# PowerMeasure.net
KiCad netlist of a schematic drawn in Altium Designer
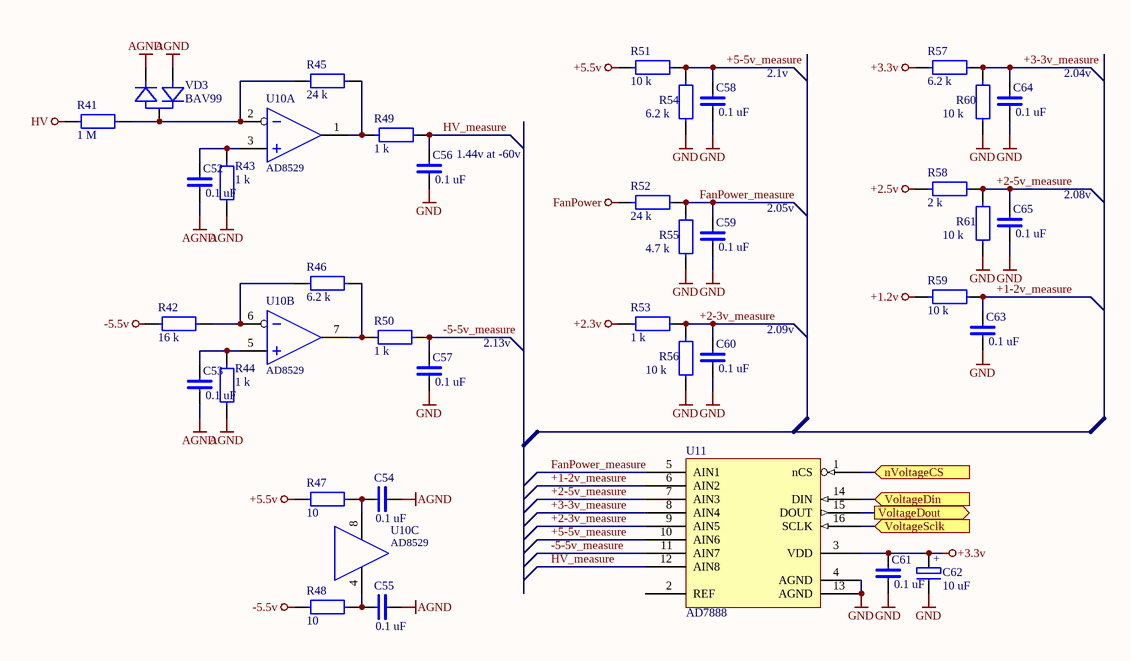
[diagram p0: PowerMeasure.SchDoc]

(export (version "E")
  (design (tool "Eeschema 10.0.6"))
  (components
    (comp (ref "C52") (value "0.1 uF") (footprint "0603") (libsource (lib "*") (part "C")))
    (comp (ref "C53") (value "0.1 uF") (footprint "0603") (libsource (lib "*") (part "C")))
    (comp (ref "C54") (value "0.1 uF") (libsource (lib "Adevice") (part "c")))
    (comp (ref "C55") (value "0.1 uF") (libsource (lib "Adevice") (part "c")))
    (comp (ref "C56") (value "0.1 uF") (footprint "0603") (libsource (lib "*") (part "C")))
    (comp (ref "C57") (value "0.1 uF") (footprint "0603") (libsource (lib "*") (part "C")))
    (comp (ref "C58") (value "0.1 uF") (footprint "0603") (libsource (lib "*") (part "C")))
    (comp (ref "C59") (value "0.1 uF") (footprint "0603") (libsource (lib "*") (part "C")))
    (comp (ref "C60") (value "0.1 uF") (footprint "0603") (libsource (lib "*") (part "C")))
    (comp (ref "C61") (value "0.1 uF") (footprint "0603") (libsource (lib "*") (part "C")))
    (comp (ref "C62") (value "10 uF") (footprint "CP3216") (libsource (lib "*") (part "C POL")))
    (comp (ref "C63") (value "0.1 uF") (footprint "0603") (libsource (lib "*") (part "C")))
    (comp (ref "C64") (value "0.1 uF") (footprint "0603") (libsource (lib "*") (part "C")))
    (comp (ref "C65") (value "0.1 uF") (footprint "0603") (libsource (lib "*") (part "C")))
    (comp (ref "R41") (value "1 M") (footprint "1206") (libsource (lib "Adevice") (part "R")))
    (comp (ref "R42") (value "16 k") (footprint "1206") (libsource (lib "Adevice") (part "R")))
    (comp (ref "R43") (value "1 k") (footprint "0603") (libsource (lib "Adevice") (part "R")))
    (comp (ref "R44") (value "1 k") (footprint "0603") (libsource (lib "Adevice") (part "R")))
    (comp (ref "R45") (value "24 k") (footprint "1206") (libsource (lib "Adevice") (part "R")))
    (comp (ref "R46") (value "6.2 k") (footprint "1206") (libsource (lib "Adevice") (part "R")))
    (comp (ref "R47") (value "10") (footprint "0603") (libsource (lib "Adevice") (part "R")))
    (comp (ref "R48") (value "10") (footprint "0603") (libsource (lib "Adevice") (part "R")))
    (comp (ref "R49") (value "1 k") (footprint "0603") (libsource (lib "*") (part "R")))
    (comp (ref "R50") (value "1 k") (footprint "0603") (libsource (lib "*") (part "R")))
    (comp (ref "R51") (value "10 k") (footprint "0603") (libsource (lib "*") (part "R")))
    (comp (ref "R52") (value "24 k") (footprint "1206") (libsource (lib "*") (part "R")))
    (comp (ref "R53") (value "1 k") (footprint "0603") (libsource (lib "*") (part "R")))
    (comp (ref "R54") (value "6.2 k") (footprint "1206") (libsource (lib "*") (part "R")))
    (comp (ref "R55") (value "4.7 k") (footprint "1206") (libsource (lib "*") (part "R")))
    (comp (ref "R56") (value "10 k") (footprint "0603") (libsource (lib "*") (part "R")))
    (comp (ref "R57") (value "6.2 k") (footprint "1206") (libsource (lib "*") (part "R")))
    (comp (ref "R58") (value "2 k") (footprint "1206") (libsource (lib "*") (part "R")))
    (comp (ref "R59") (value "10 k") (footprint "0603") (libsource (lib "*") (part "R")))
    (comp (ref "R60") (value "10 k") (footprint "0603") (libsource (lib "*") (part "R")))
    (comp (ref "R61") (value "10 k") (footprint "0603") (libsource (lib "*") (part "R")))
    (comp (ref "U10")
      (value "AD8529")
      (footprint "8SOIC150")
      (description "8 MHz Rail-to-Rail Operational Amplifiers")
      (libsource (lib "Mylib") (part "AD8529"))
    )
    (comp (ref "U11")
      (value "AD7888")
      (footprint "16SOIC150")
      (description "8-Channel, 125 kSPS, 12-Bit ADC")
      (libsource (lib "Mylib") (part "AD7888"))
    )
    (comp (ref "VD3")
      (value "BAV99")
      (footprint "SOT-23")
      (description "Double diode")
      (libsource (lib "Vdiode") (part "BAV99"))
    )
  )
  (nets
    (net (code "1") (name "+1.2v") (class "Default")
      (node (ref "R59") (pin "2") (pinfunction "2_2") (pintype "passive"))
    )
    (net (code "2") (name "+2.3v") (class "Default")
      (node (ref "R53") (pin "2") (pinfunction "2_2") (pintype "passive"))
    )
    (net (code "3") (name "+2.5v") (class "Default")
      (node (ref "R58") (pin "2") (pinfunction "2_2") (pintype "passive"))
    )
    (net (code "4") (name "+3.3v") (class "Default")
      (node (ref "C61") (pin "2") (pinfunction "2_2") (pintype "passive"))
      (node (ref "C62") (pin "+") (pinfunction "+_+") (pintype "passive"))
      (node (ref "R57") (pin "2") (pinfunction "2_2") (pintype "passive"))
      (node (ref "U11") (pin "3") (pinfunction "VDD_3") (pintype "passive"))
    )
    (net (code "5") (name "+5.5v") (class "Default")
      (node (ref "R47") (pin "1") (pinfunction "1_1") (pintype "passive"))
      (node (ref "R51") (pin "2") (pinfunction "2_2") (pintype "passive"))
    )
    (net (code "6") (name "-5.5v") (class "Default")
      (node (ref "R42") (pin "1") (pinfunction "1_1") (pintype "passive"))
      (node (ref "R48") (pin "1") (pinfunction "1_1") (pintype "passive"))
    )
    (net (code "7") (name "/+1-2v_measure") (class "Default")
      (node (ref "C63") (pin "2") (pinfunction "2_2") (pintype "passive"))
      (node (ref "R59") (pin "1") (pinfunction "1_1") (pintype "passive"))
      (node (ref "U11") (pin "6") (pinfunction "AIN2_6") (pintype "passive"))
    )
    (net (code "8") (name "/+2-3v_measure") (class "Default")
      (node (ref "C60") (pin "2") (pinfunction "2_2") (pintype "passive"))
      (node (ref "R53") (pin "1") (pinfunction "1_1") (pintype "passive"))
      (node (ref "R56") (pin "2") (pinfunction "2_2") (pintype "passive"))
      (node (ref "U11") (pin "9") (pinfunction "AIN5_9") (pintype "passive"))
    )
    (net (code "9") (name "/+2-5v_measure") (class "Default")
      (node (ref "C65") (pin "2") (pinfunction "2_2") (pintype "passive"))
      (node (ref "R58") (pin "1") (pinfunction "1_1") (pintype "passive"))
      (node (ref "R61") (pin "2") (pinfunction "2_2") (pintype "passive"))
      (node (ref "U11") (pin "7") (pinfunction "AIN3_7") (pintype "passive"))
    )
    (net (code "10") (name "/+3-3v_measure") (class "Default")
      (node (ref "C64") (pin "2") (pinfunction "2_2") (pintype "passive"))
      (node (ref "R57") (pin "1") (pinfunction "1_1") (pintype "passive"))
      (node (ref "R60") (pin "2") (pinfunction "2_2") (pintype "passive"))
      (node (ref "U11") (pin "8") (pinfunction "AIN4_8") (pintype "passive"))
    )
    (net (code "11") (name "/+5-5v_measure") (class "Default")
      (node (ref "C58") (pin "2") (pinfunction "2_2") (pintype "passive"))
      (node (ref "R51") (pin "1") (pinfunction "1_1") (pintype "passive"))
      (node (ref "R54") (pin "2") (pinfunction "2_2") (pintype "passive"))
      (node (ref "U11") (pin "10") (pinfunction "AIN6_10") (pintype "passive"))
    )
    (net (code "12") (name "/-5-5v_measure") (class "Default")
      (node (ref "C57") (pin "2") (pinfunction "2_2") (pintype "passive"))
      (node (ref "R50") (pin "2") (pinfunction "2_2") (pintype "passive"))
      (node (ref "U11") (pin "11") (pinfunction "AIN7_11") (pintype "passive"))
    )
    (net (code "13") (name "/FanPower_measure") (class "Default")
      (node (ref "C59") (pin "2") (pinfunction "2_2") (pintype "passive"))
      (node (ref "R52") (pin "1") (pinfunction "1_1") (pintype "passive"))
      (node (ref "R55") (pin "2") (pinfunction "2_2") (pintype "passive"))
      (node (ref "U11") (pin "5") (pinfunction "AIN1_5") (pintype "passive"))
    )
    (net (code "14") (name "/HV_measure") (class "Default")
      (node (ref "C56") (pin "2") (pinfunction "2_2") (pintype "passive"))
      (node (ref "R49") (pin "1") (pinfunction "1_1") (pintype "passive"))
      (node (ref "U11") (pin "12") (pinfunction "AIN8_12") (pintype "passive"))
    )
    (net (code "15") (name "/VoltageDin") (class "Default")
      (node (ref "U11") (pin "14") (pinfunction "DIN_14") (pintype "input"))
    )
    (net (code "16") (name "/VoltageDout") (class "Default")
      (node (ref "U11") (pin "15") (pinfunction "DOUT_15") (pintype "output"))
    )
    (net (code "17") (name "/VoltageSclk") (class "Default")
      (node (ref "U11") (pin "16") (pinfunction "SCLK_16") (pintype "input"))
    )
    (net (code "18") (name "/nVoltageCS") (class "Default")
      (node (ref "U11") (pin "1") (pinfunction "nCS_1") (pintype "input"))
    )
    (net (code "19") (name "AGND") (class "Default")
      (node (ref "C52") (pin "1") (pinfunction "1_1") (pintype "passive"))
      (node (ref "C53") (pin "1") (pinfunction "1_1") (pintype "passive"))
      (node (ref "C54") (pin "1") (pinfunction "1_1") (pintype "passive"))
      (node (ref "C55") (pin "1") (pinfunction "1_1") (pintype "passive"))
      (node (ref "R43") (pin "1") (pinfunction "1_1") (pintype "passive"))
      (node (ref "R44") (pin "1") (pinfunction "1_1") (pintype "passive"))
      (node (ref "VD3") (pin "1") (pinfunction "1_1") (pintype "passive"))
      (node (ref "VD3") (pin "2") (pinfunction "2_2") (pintype "passive"))
    )
    (net (code "20") (name "FanPower") (class "Default")
      (node (ref "R52") (pin "2") (pinfunction "2_2") (pintype "passive"))
    )
    (net (code "21") (name "GND") (class "Default")
      (node (ref "C56") (pin "1") (pinfunction "1_1") (pintype "passive"))
      (node (ref "C57") (pin "1") (pinfunction "1_1") (pintype "passive"))
      (node (ref "C58") (pin "1") (pinfunction "1_1") (pintype "passive"))
      (node (ref "C59") (pin "1") (pinfunction "1_1") (pintype "passive"))
      (node (ref "C60") (pin "1") (pinfunction "1_1") (pintype "passive"))
      (node (ref "C61") (pin "1") (pinfunction "1_1") (pintype "passive"))
      (node (ref "C62") (pin "-") (pinfunction "-_-") (pintype "passive"))
      (node (ref "C63") (pin "1") (pinfunction "1_1") (pintype "passive"))
      (node (ref "C64") (pin "1") (pinfunction "1_1") (pintype "passive"))
      (node (ref "C65") (pin "1") (pinfunction "1_1") (pintype "passive"))
      (node (ref "R54") (pin "1") (pinfunction "1_1") (pintype "passive"))
      (node (ref "R55") (pin "1") (pinfunction "1_1") (pintype "passive"))
      (node (ref "R56") (pin "1") (pinfunction "1_1") (pintype "passive"))
      (node (ref "R60") (pin "1") (pinfunction "1_1") (pintype "passive"))
      (node (ref "R61") (pin "1") (pinfunction "1_1") (pintype "passive"))
      (node (ref "U11") (pin "13") (pinfunction "AGND_13") (pintype "passive"))
      (node (ref "U11") (pin "4") (pinfunction "AGND_4") (pintype "passive"))
    )
    (net (code "22") (name "HV") (class "Default")
      (node (ref "R41") (pin "1") (pinfunction "1_1") (pintype "passive"))
    )
    (net (code "23") (name "Net-(U10A-IN+)") (class "Default")
      (node (ref "C52") (pin "2") (pinfunction "2_2") (pintype "passive"))
      (node (ref "R43") (pin "2") (pinfunction "2_2") (pintype "passive"))
      (node (ref "U10") (pin "3") (pinfunction "IN+_3") (pintype "passive"))
    )
    (net (code "24") (name "Net-(U10A-IN-)") (class "Default")
      (node (ref "R41") (pin "2") (pinfunction "2_2") (pintype "passive"))
      (node (ref "R45") (pin "1") (pinfunction "1_1") (pintype "passive"))
      (node (ref "U10") (pin "2") (pinfunction "IN-_2") (pintype "passive"))
      (node (ref "VD3") (pin "3") (pinfunction "3_3") (pintype "passive"))
    )
    (net (code "25") (name "Net-(U10A-OUT)") (class "Default")
      (node (ref "R45") (pin "2") (pinfunction "2_2") (pintype "passive"))
      (node (ref "R49") (pin "2") (pinfunction "2_2") (pintype "passive"))
      (node (ref "U10") (pin "1") (pinfunction "OUT_1") (pintype "passive"))
    )
    (net (code "26") (name "Net-(U10B-IN+)") (class "Default")
      (node (ref "C53") (pin "2") (pinfunction "2_2") (pintype "passive"))
      (node (ref "R44") (pin "2") (pinfunction "2_2") (pintype "passive"))
      (node (ref "U10") (pin "5") (pinfunction "IN+_5") (pintype "passive"))
    )
    (net (code "27") (name "Net-(U10B-IN-)") (class "Default")
      (node (ref "R42") (pin "2") (pinfunction "2_2") (pintype "passive"))
      (node (ref "R46") (pin "1") (pinfunction "1_1") (pintype "passive"))
      (node (ref "U10") (pin "6") (pinfunction "IN-_6") (pintype "passive"))
    )
    (net (code "28") (name "Net-(U10B-OUT)") (class "Default")
      (node (ref "R46") (pin "2") (pinfunction "2_2") (pintype "passive"))
      (node (ref "R50") (pin "1") (pinfunction "1_1") (pintype "passive"))
      (node (ref "U10") (pin "7") (pinfunction "OUT_7") (pintype "passive"))
    )
    (net (code "29") (name "Net-(U10C-V+)") (class "Default")
      (node (ref "C54") (pin "2") (pinfunction "2_2") (pintype "passive"))
      (node (ref "R47") (pin "2") (pinfunction "2_2") (pintype "passive"))
      (node (ref "U10") (pin "8") (pinfunction "V+_8") (pintype "passive"))
    )
    (net (code "30") (name "Net-(U10C-V-)") (class "Default")
      (node (ref "C55") (pin "2") (pinfunction "2_2") (pintype "passive"))
      (node (ref "R48") (pin "2") (pinfunction "2_2") (pintype "passive"))
      (node (ref "U10") (pin "4") (pinfunction "V-_4") (pintype "passive"))
    )
    (net (code "31") (name "unconnected-(U11-REF-Pad2)") (class "Default")
      (node (ref "U11") (pin "2") (pinfunction "REF_2") (pintype "passive"))
    )
  )
)
